# 3-channel_geo_amplifier.net
KiCad netlist of a schematic drawn in EAGLE
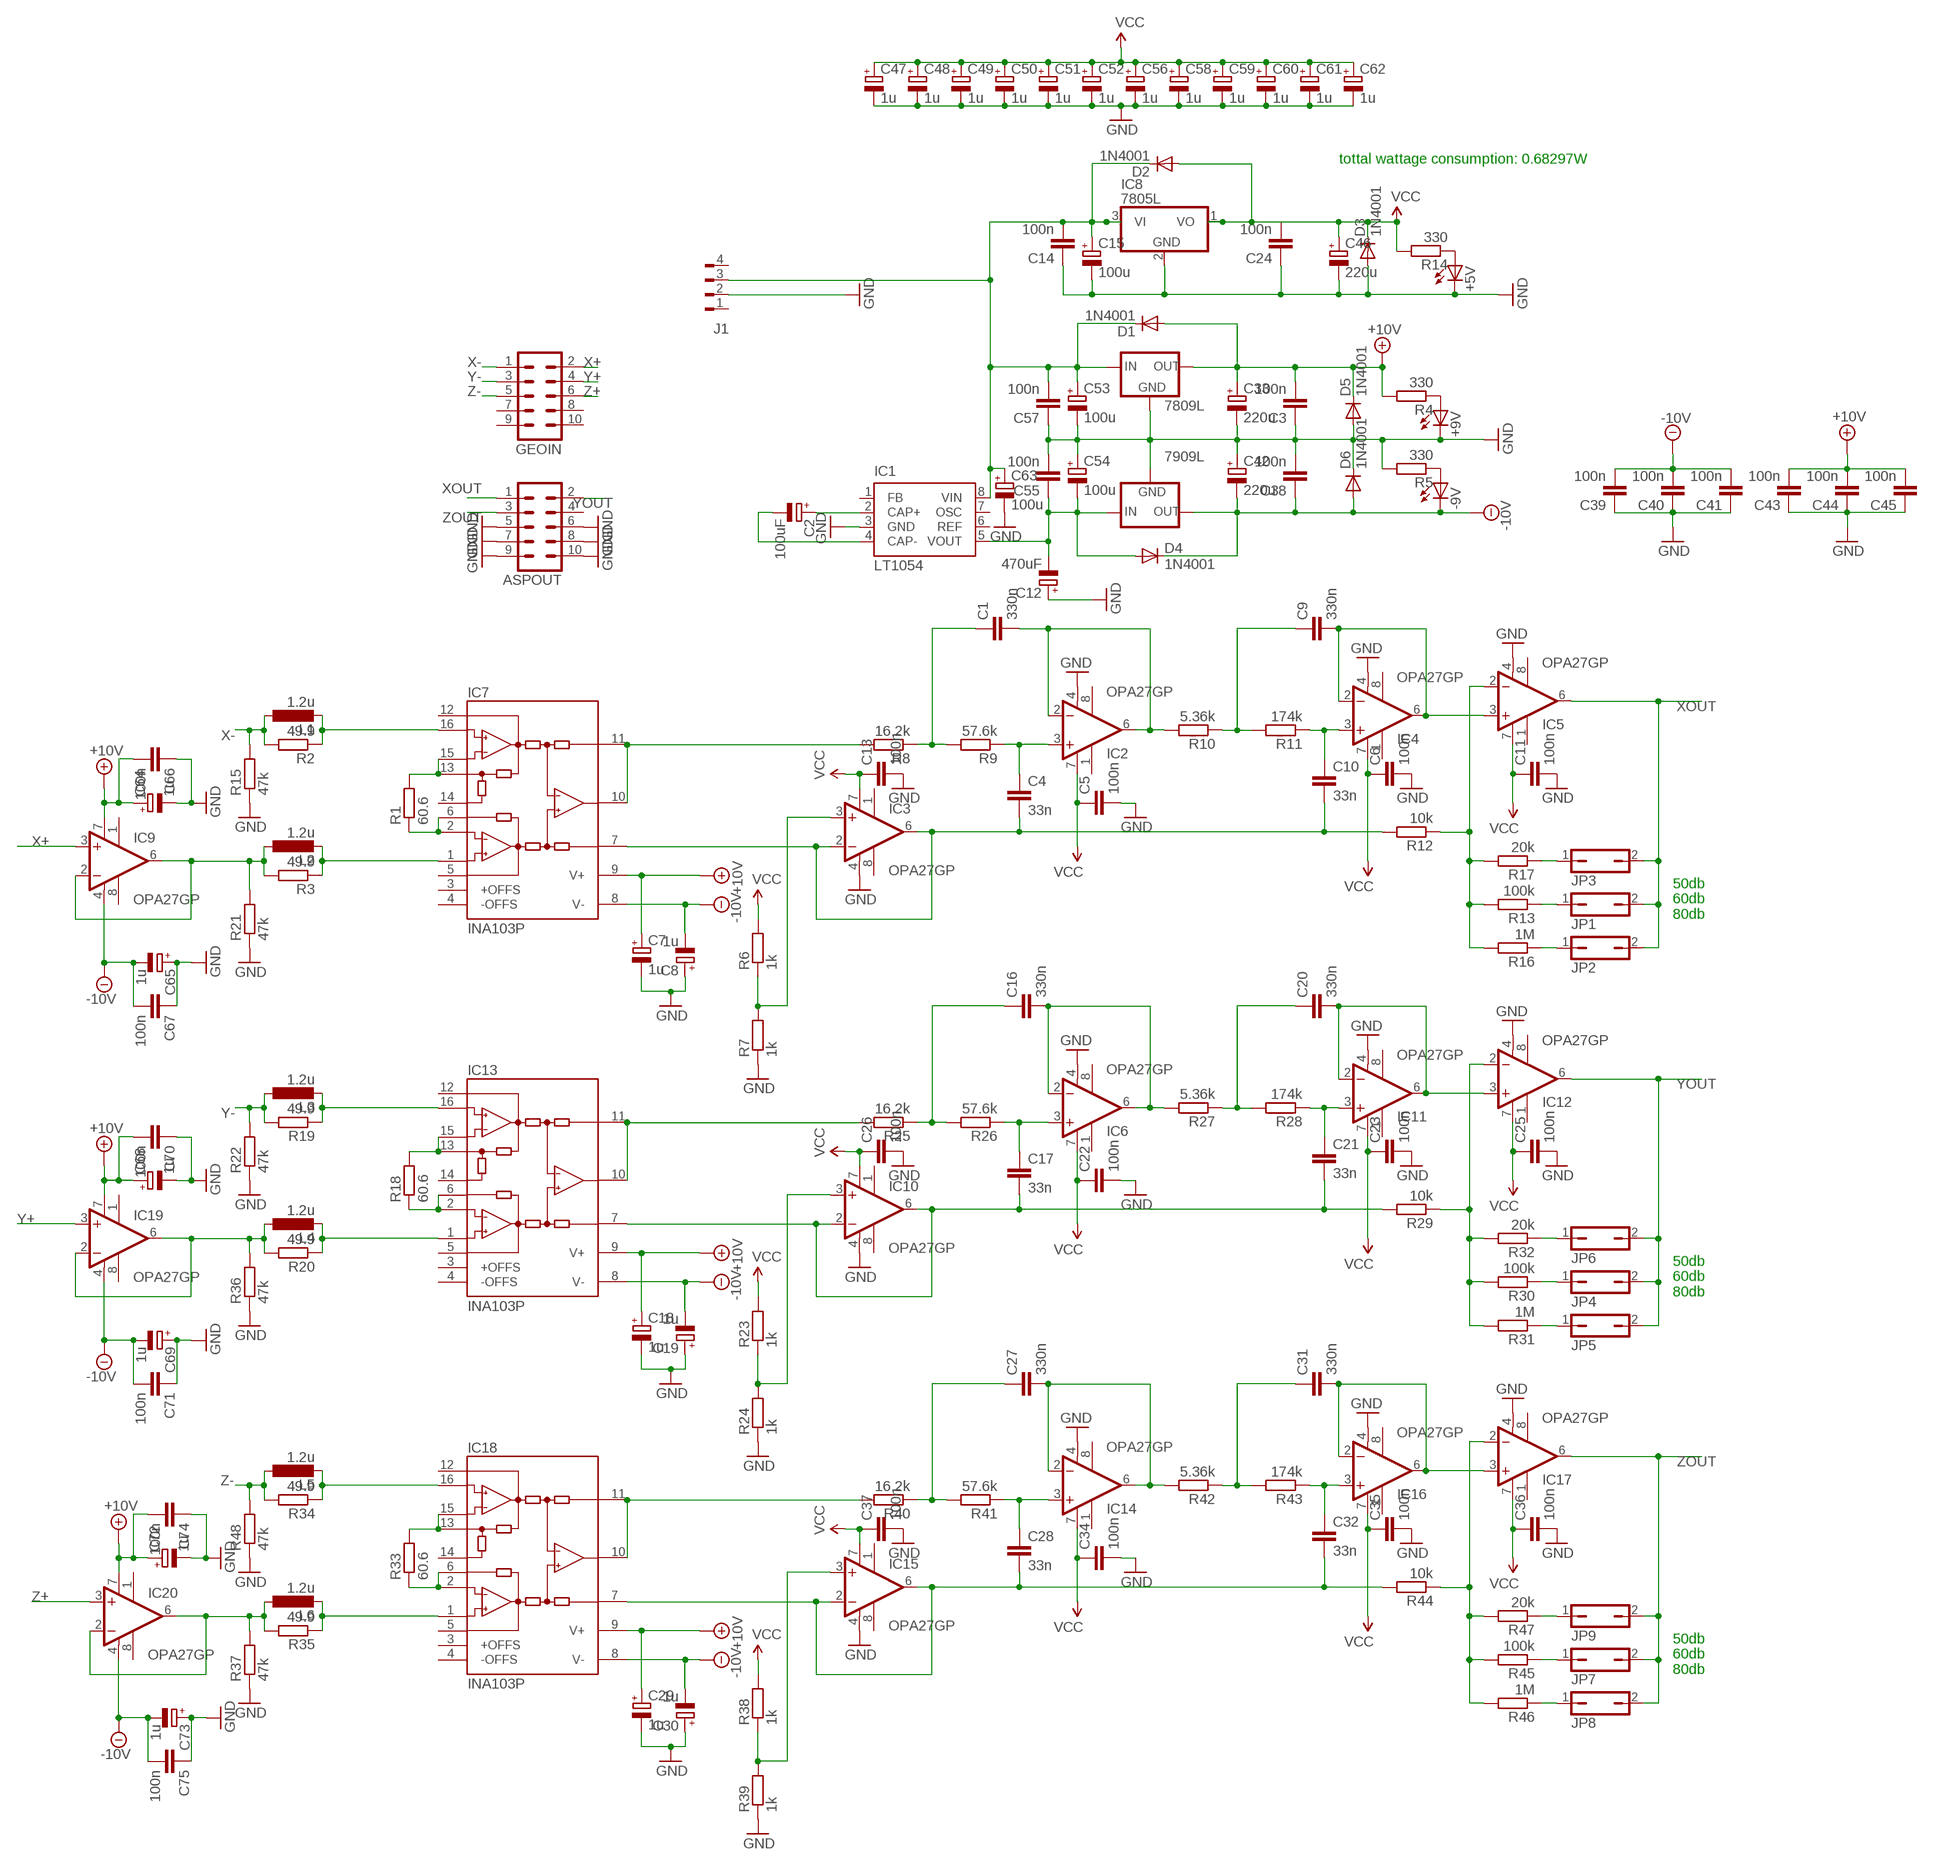
[diagram p0: schematic, sheet 1]

(export (version "E")
  (design (tool "Eeschema 10.0.6"))
  (components
    (comp (ref "+5V")
      (value "LED3MM")
      (footprint "eagle-import:LED3MM")
      (libsource (lib "eagle-import") (part "LED3MM"))
    )
    (comp (ref "+9V")
      (value "LED3MM")
      (footprint "eagle-import:LED3MM")
      (libsource (lib "eagle-import") (part "LED3MM"))
    )
    (comp (ref "-9V")
      (value "LED3MM")
      (footprint "eagle-import:LED3MM")
      (libsource (lib "eagle-import") (part "LED3MM"))
    )
    (comp (ref "7809L")
      (value "78LXX")
      (footprint "eagle-import:78LXX")
      (libsource (lib "eagle-import") (part "78LXX"))
    )
    (comp (ref "7909L")
      (value "79LXX")
      (footprint "eagle-import:79LXX")
      (libsource (lib "eagle-import") (part "79LXX"))
    )
    (comp (ref "ASPOUT")
      (value "ML10")
      (footprint "eagle-import:ML10")
      (libsource (lib "eagle-import") (part "ML10"))
    )
    (comp (ref "C1")
      (value "330n")
      (footprint "eagle-import:C050-025X075")
      (libsource (lib "eagle-import") (part "C-EU050-025X075"))
    )
    (comp (ref "C2")
      (value "100uF")
      (footprint "eagle-import:E2,5-7")
      (libsource (lib "eagle-import") (part "CPOL-EUE2.5-7"))
    )
    (comp (ref "C3")
      (value "100n")
      (footprint "eagle-import:C050-025X075")
      (libsource (lib "eagle-import") (part "C-EU050-025X075"))
    )
    (comp (ref "C4")
      (value "33n")
      (footprint "eagle-import:C050-025X075")
      (libsource (lib "eagle-import") (part "C-EU050-025X075"))
    )
    (comp (ref "C5")
      (value "100n")
      (footprint "eagle-import:C050-025X075")
      (libsource (lib "eagle-import") (part "C-EU050-025X075"))
    )
    (comp (ref "C6")
      (value "100n")
      (footprint "eagle-import:C050-025X075")
      (libsource (lib "eagle-import") (part "C-EU050-025X075"))
    )
    (comp (ref "C7")
      (value "1u")
      (footprint "eagle-import:B45181A")
      (libsource (lib "eagle-import") (part "CPOL-EUB45181A"))
    )
    (comp (ref "C8")
      (value "1u")
      (footprint "eagle-import:B45181A")
      (libsource (lib "eagle-import") (part "CPOL-EUB45181A"))
    )
    (comp (ref "C9")
      (value "330n")
      (footprint "eagle-import:C050-025X075")
      (libsource (lib "eagle-import") (part "C-EU050-025X075"))
    )
    (comp (ref "C10")
      (value "33n")
      (footprint "eagle-import:C050-025X075")
      (libsource (lib "eagle-import") (part "C-EU050-025X075"))
    )
    (comp (ref "C11")
      (value "100n")
      (footprint "eagle-import:C050-025X075")
      (libsource (lib "eagle-import") (part "C-EU050-025X075"))
    )
    (comp (ref "C12")
      (value "470uF")
      (footprint "eagle-import:E5-8,5")
      (libsource (lib "eagle-import") (part "CPOL-EUE5-8.5"))
    )
    (comp (ref "C13")
      (value "100n")
      (footprint "eagle-import:C050-025X075")
      (libsource (lib "eagle-import") (part "C-EU050-025X075"))
    )
    (comp (ref "C14")
      (value "100n")
      (footprint "eagle-import:C050-025X075")
      (libsource (lib "eagle-import") (part "C-EU050-025X075"))
    )
    (comp (ref "C15")
      (value "100u")
      (footprint "eagle-import:E2,5-7")
      (libsource (lib "eagle-import") (part "CPOL-EUE2.5-7"))
    )
    (comp (ref "C16")
      (value "330n")
      (footprint "eagle-import:C050-025X075")
      (libsource (lib "eagle-import") (part "C-EU050-025X075"))
    )
    (comp (ref "C17")
      (value "33n")
      (footprint "eagle-import:C050-025X075")
      (libsource (lib "eagle-import") (part "C-EU050-025X075"))
    )
    (comp (ref "C18")
      (value "1u")
      (footprint "eagle-import:B45181A")
      (libsource (lib "eagle-import") (part "CPOL-EUB45181A"))
    )
    (comp (ref "C19")
      (value "1u")
      (footprint "eagle-import:B45181A")
      (libsource (lib "eagle-import") (part "CPOL-EUB45181A"))
    )
    (comp (ref "C20")
      (value "330n")
      (footprint "eagle-import:C050-025X075")
      (libsource (lib "eagle-import") (part "C-EU050-025X075"))
    )
    (comp (ref "C21")
      (value "33n")
      (footprint "eagle-import:C050-025X075")
      (libsource (lib "eagle-import") (part "C-EU050-025X075"))
    )
    (comp (ref "C22")
      (value "100n")
      (footprint "eagle-import:C050-025X075")
      (libsource (lib "eagle-import") (part "C-EU050-025X075"))
    )
    (comp (ref "C23")
      (value "100n")
      (footprint "eagle-import:C050-025X075")
      (libsource (lib "eagle-import") (part "C-EU050-025X075"))
    )
    (comp (ref "C24")
      (value "100n")
      (footprint "eagle-import:C050-025X075")
      (libsource (lib "eagle-import") (part "C-EU050-025X075"))
    )
    (comp (ref "C25")
      (value "100n")
      (footprint "eagle-import:C050-025X075")
      (libsource (lib "eagle-import") (part "C-EU050-025X075"))
    )
    (comp (ref "C26")
      (value "100n")
      (footprint "eagle-import:C050-025X075")
      (libsource (lib "eagle-import") (part "C-EU050-025X075"))
    )
    (comp (ref "C27")
      (value "330n")
      (footprint "eagle-import:C050-025X075")
      (libsource (lib "eagle-import") (part "C-EU050-025X075"))
    )
    (comp (ref "C28")
      (value "33n")
      (footprint "eagle-import:C050-025X075")
      (libsource (lib "eagle-import") (part "C-EU050-025X075"))
    )
    (comp (ref "C29")
      (value "1u")
      (footprint "eagle-import:B45181A")
      (libsource (lib "eagle-import") (part "CPOL-EUB45181A"))
    )
    (comp (ref "C30")
      (value "1u")
      (footprint "eagle-import:B45181A")
      (libsource (lib "eagle-import") (part "CPOL-EUB45181A"))
    )
    (comp (ref "C31")
      (value "330n")
      (footprint "eagle-import:C050-025X075")
      (libsource (lib "eagle-import") (part "C-EU050-025X075"))
    )
    (comp (ref "C32")
      (value "33n")
      (footprint "eagle-import:C050-025X075")
      (libsource (lib "eagle-import") (part "C-EU050-025X075"))
    )
    (comp (ref "C33")
      (value "220u")
      (footprint "eagle-import:E2,5-5")
      (libsource (lib "eagle-import") (part "CPOL-EUE2.5-5"))
    )
    (comp (ref "C34")
      (value "100n")
      (footprint "eagle-import:C050-025X075")
      (libsource (lib "eagle-import") (part "C-EU050-025X075"))
    )
    (comp (ref "C35")
      (value "100n")
      (footprint "eagle-import:C050-025X075")
      (libsource (lib "eagle-import") (part "C-EU050-025X075"))
    )
    (comp (ref "C36")
      (value "100n")
      (footprint "eagle-import:C050-025X075")
      (libsource (lib "eagle-import") (part "C-EU050-025X075"))
    )
    (comp (ref "C37")
      (value "100n")
      (footprint "eagle-import:C050-025X075")
      (libsource (lib "eagle-import") (part "C-EU050-025X075"))
    )
    (comp (ref "C38")
      (value "100n")
      (footprint "eagle-import:C050-025X075")
      (libsource (lib "eagle-import") (part "C-EU050-025X075"))
    )
    (comp (ref "C39")
      (value "100n")
      (footprint "eagle-import:C050-025X075")
      (libsource (lib "eagle-import") (part "C-EU050-025X075"))
    )
    (comp (ref "C40")
      (value "100n")
      (footprint "eagle-import:C050-025X075")
      (libsource (lib "eagle-import") (part "C-EU050-025X075"))
    )
    (comp (ref "C41")
      (value "100n")
      (footprint "eagle-import:C050-025X075")
      (libsource (lib "eagle-import") (part "C-EU050-025X075"))
    )
    (comp (ref "C42")
      (value "220u")
      (footprint "eagle-import:E2,5-5")
      (libsource (lib "eagle-import") (part "CPOL-EUE2.5-5"))
    )
    (comp (ref "C43")
      (value "100n")
      (footprint "eagle-import:C050-025X075")
      (libsource (lib "eagle-import") (part "C-EU050-025X075"))
    )
    (comp (ref "C44")
      (value "100n")
      (footprint "eagle-import:C050-025X075")
      (libsource (lib "eagle-import") (part "C-EU050-025X075"))
    )
    (comp (ref "C45")
      (value "100n")
      (footprint "eagle-import:C050-025X075")
      (libsource (lib "eagle-import") (part "C-EU050-025X075"))
    )
    (comp (ref "C46")
      (value "220u")
      (footprint "eagle-import:E2,5-7")
      (libsource (lib "eagle-import") (part "CPOL-EUE2.5-7"))
    )
    (comp (ref "C47")
      (value "1u")
      (footprint "eagle-import:B45181A")
      (libsource (lib "eagle-import") (part "CPOL-EUB45181A"))
    )
    (comp (ref "C48")
      (value "1u")
      (footprint "eagle-import:B45181A")
      (libsource (lib "eagle-import") (part "CPOL-EUB45181A"))
    )
    (comp (ref "C49")
      (value "1u")
      (footprint "eagle-import:B45181A")
      (libsource (lib "eagle-import") (part "CPOL-EUB45181A"))
    )
    (comp (ref "C50")
      (value "1u")
      (footprint "eagle-import:B45181A")
      (libsource (lib "eagle-import") (part "CPOL-EUB45181A"))
    )
    (comp (ref "C51")
      (value "1u")
      (footprint "eagle-import:B45181A")
      (libsource (lib "eagle-import") (part "CPOL-EUB45181A"))
    )
    (comp (ref "C52")
      (value "1u")
      (footprint "eagle-import:B45181A")
      (libsource (lib "eagle-import") (part "CPOL-EUB45181A"))
    )
    (comp (ref "C53")
      (value "100u")
      (footprint "eagle-import:E2,5-5")
      (libsource (lib "eagle-import") (part "CPOL-EUE2.5-5"))
    )
    (comp (ref "C54")
      (value "100u")
      (footprint "eagle-import:E2,5-5")
      (libsource (lib "eagle-import") (part "CPOL-EUE2.5-5"))
    )
    (comp (ref "C55")
      (value "100n")
      (footprint "eagle-import:C050-025X075")
      (libsource (lib "eagle-import") (part "C-EU050-025X075"))
    )
    (comp (ref "C56")
      (value "1u")
      (footprint "eagle-import:B45181A")
      (libsource (lib "eagle-import") (part "CPOL-EUB45181A"))
    )
    (comp (ref "C57")
      (value "100n")
      (footprint "eagle-import:C050-025X075")
      (libsource (lib "eagle-import") (part "C-EU050-025X075"))
    )
    (comp (ref "C58")
      (value "1u")
      (footprint "eagle-import:B45181A")
      (libsource (lib "eagle-import") (part "CPOL-EUB45181A"))
    )
    (comp (ref "C59")
      (value "1u")
      (footprint "eagle-import:B45181A")
      (libsource (lib "eagle-import") (part "CPOL-EUB45181A"))
    )
    (comp (ref "C60")
      (value "1u")
      (footprint "eagle-import:B45181A")
      (libsource (lib "eagle-import") (part "CPOL-EUB45181A"))
    )
    (comp (ref "C61")
      (value "1u")
      (footprint "eagle-import:B45181A")
      (libsource (lib "eagle-import") (part "CPOL-EUB45181A"))
    )
    (comp (ref "C62")
      (value "1u")
      (footprint "eagle-import:B45181A")
      (libsource (lib "eagle-import") (part "CPOL-EUB45181A"))
    )
    (comp (ref "C63")
      (value "100u")
      (footprint "eagle-import:E2,5-5")
      (libsource (lib "eagle-import") (part "CPOL-EUE2.5-5"))
    )
    (comp (ref "C64")
      (value "1u")
      (footprint "eagle-import:B45181A")
      (libsource (lib "eagle-import") (part "CPOL-EUB45181A"))
    )
    (comp (ref "C65")
      (value "1u")
      (footprint "eagle-import:B45181A")
      (libsource (lib "eagle-import") (part "CPOL-EUB45181A"))
    )
    (comp (ref "C66")
      (value "100n")
      (footprint "eagle-import:C050-025X075")
      (libsource (lib "eagle-import") (part "C-EU050-025X075"))
    )
    (comp (ref "C67")
      (value "100n")
      (footprint "eagle-import:C050-025X075")
      (libsource (lib "eagle-import") (part "C-EU050-025X075"))
    )
    (comp (ref "C68")
      (value "1u")
      (footprint "eagle-import:B45181A")
      (libsource (lib "eagle-import") (part "CPOL-EUB45181A"))
    )
    (comp (ref "C69")
      (value "1u")
      (footprint "eagle-import:B45181A")
      (libsource (lib "eagle-import") (part "CPOL-EUB45181A"))
    )
    (comp (ref "C70")
      (value "100n")
      (footprint "eagle-import:C050-025X075")
      (libsource (lib "eagle-import") (part "C-EU050-025X075"))
    )
    (comp (ref "C71")
      (value "100n")
      (footprint "eagle-import:C050-025X075")
      (libsource (lib "eagle-import") (part "C-EU050-025X075"))
    )
    (comp (ref "C72")
      (value "1u")
      (footprint "eagle-import:B45181A")
      (libsource (lib "eagle-import") (part "CPOL-EUB45181A"))
    )
    (comp (ref "C73")
      (value "1u")
      (footprint "eagle-import:B45181A")
      (libsource (lib "eagle-import") (part "CPOL-EUB45181A"))
    )
    (comp (ref "C74")
      (value "100n")
      (footprint "eagle-import:C050-025X075")
      (libsource (lib "eagle-import") (part "C-EU050-025X075"))
    )
    (comp (ref "C75")
      (value "100n")
      (footprint "eagle-import:C050-025X075")
      (libsource (lib "eagle-import") (part "C-EU050-025X075"))
    )
    (comp (ref "D1")
      (value "1N4001")
      (footprint "eagle-import:DO41-10")
      (libsource (lib "eagle-import") (part "1N4004"))
    )
    (comp (ref "D2")
      (value "1N4001")
      (footprint "eagle-import:DO41-10")
      (libsource (lib "eagle-import") (part "1N4004"))
    )
    (comp (ref "D3")
      (value "1N4001")
      (footprint "eagle-import:DO41-10")
      (libsource (lib "eagle-import") (part "1N4004"))
    )
    (comp (ref "D4")
      (value "1N4001")
      (footprint "eagle-import:DO41-10")
      (libsource (lib "eagle-import") (part "1N4004"))
    )
    (comp (ref "D5")
      (value "1N4001")
      (footprint "eagle-import:DO41-10")
      (libsource (lib "eagle-import") (part "1N4004"))
    )
    (comp (ref "D6")
      (value "1N4001")
      (footprint "eagle-import:DO41-10")
      (libsource (lib "eagle-import") (part "1N4004"))
    )
    (comp (ref "GEOIN")
      (value "ML10")
      (footprint "eagle-import:ML10")
      (libsource (lib "eagle-import") (part "ML10"))
    )
    (comp (ref "IC1")
      (value "LT1054")
      (footprint "eagle-import:DIL8")
      (libsource (lib "eagle-import") (part "LT1054"))
    )
    (comp (ref "IC2")
      (value "OPA27GP")
      (footprint "eagle-import:DIL08")
      (libsource (lib "eagle-import") (part "OPA?GP27"))
    )
    (comp (ref "IC3")
      (value "OPA27GP")
      (footprint "eagle-import:DIL08")
      (libsource (lib "eagle-import") (part "OPA?GP27"))
    )
    (comp (ref "IC4")
      (value "OPA27GP")
      (footprint "eagle-import:DIL08")
      (libsource (lib "eagle-import") (part "OPA?GP27"))
    )
    (comp (ref "IC5")
      (value "OPA27GP")
      (footprint "eagle-import:DIL08")
      (libsource (lib "eagle-import") (part "OPA?GP27"))
    )
    (comp (ref "IC6")
      (value "OPA27GP")
      (footprint "eagle-import:DIL08")
      (libsource (lib "eagle-import") (part "OPA?GP27"))
    )
    (comp (ref "IC7")
      (value "INA103P")
      (footprint "eagle-import:DIL16")
      (fields (field (name "MF") "TEXAS INSTRUMENTS") (field (name "MPN") "INA103KP"))
      (libsource (lib "eagle-import") (part "INA103P"))
    )
    (comp (ref "IC8")
      (value "7805L")
      (footprint "eagle-import:TO92")
      (libsource (lib "eagle-import") (part "78L05"))
    )
    (comp (ref "IC9")
      (value "OPA27GP")
      (footprint "eagle-import:DIL08")
      (libsource (lib "eagle-import") (part "OPA?GP27"))
    )
    (comp (ref "IC10")
      (value "OPA27GP")
      (footprint "eagle-import:DIL08")
      (libsource (lib "eagle-import") (part "OPA?GP27"))
    )
    (comp (ref "IC11")
      (value "OPA27GP")
      (footprint "eagle-import:DIL08")
      (libsource (lib "eagle-import") (part "OPA?GP27"))
    )
    (comp (ref "IC12")
      (value "OPA27GP")
      (footprint "eagle-import:DIL08")
      (libsource (lib "eagle-import") (part "OPA?GP27"))
    )
    (comp (ref "IC13")
      (value "INA103P")
      (footprint "eagle-import:DIL16")
      (fields (field (name "MF") "TEXAS INSTRUMENTS") (field (name "MPN") "INA103KP"))
      (libsource (lib "eagle-import") (part "INA103P"))
    )
    (comp (ref "IC14")
      (value "OPA27GP")
      (footprint "eagle-import:DIL08")
      (libsource (lib "eagle-import") (part "OPA?GP27"))
    )
    (comp (ref "IC15")
      (value "OPA27GP")
      (footprint "eagle-import:DIL08")
      (libsource (lib "eagle-import") (part "OPA?GP27"))
    )
    (comp (ref "IC16")
      (value "OPA27GP")
      (footprint "eagle-import:DIL08")
      (libsource (lib "eagle-import") (part "OPA?GP27"))
    )
    (comp (ref "IC17")
      (value "OPA27GP")
      (footprint "eagle-import:DIL08")
      (libsource (lib "eagle-import") (part "OPA?GP27"))
    )
    (comp (ref "IC18")
      (value "INA103P")
      (footprint "eagle-import:DIL16")
      (fields (field (name "MF") "TEXAS INSTRUMENTS") (field (name "MPN") "INA103KP"))
      (libsource (lib "eagle-import") (part "INA103P"))
    )
    (comp (ref "IC19")
      (value "OPA27GP")
      (footprint "eagle-import:DIL08")
      (libsource (lib "eagle-import") (part "OPA?GP27"))
    )
    (comp (ref "IC20")
      (value "OPA27GP")
      (footprint "eagle-import:DIL08")
      (libsource (lib "eagle-import") (part "OPA?GP27"))
    )
    (comp (ref "J1")
      (value "FLOP-4W827001")
      (footprint "eagle-import:827001")
      (libsource (lib "eagle-import") (part "FLOP-4W827001"))
    )
    (comp (ref "JP1")
      (value "JP1Q")
      (footprint "eagle-import:JP1")
      (libsource (lib "eagle-import") (part "JP1Q"))
    )
    (comp (ref "JP2")
      (value "JP1Q")
      (footprint "eagle-import:JP1")
      (libsource (lib "eagle-import") (part "JP1Q"))
    )
    (comp (ref "JP3")
      (value "JP1Q")
      (footprint "eagle-import:JP1")
      (libsource (lib "eagle-import") (part "JP1Q"))
    )
    (comp (ref "JP4")
      (value "JP1Q")
      (footprint "eagle-import:JP1")
      (libsource (lib "eagle-import") (part "JP1Q"))
    )
    (comp (ref "JP5")
      (value "JP1Q")
      (footprint "eagle-import:JP1")
      (libsource (lib "eagle-import") (part "JP1Q"))
    )
    (comp (ref "JP6")
      (value "JP1Q")
      (footprint "eagle-import:JP1")
      (libsource (lib "eagle-import") (part "JP1Q"))
    )
    (comp (ref "JP7")
      (value "JP1Q")
      (footprint "eagle-import:JP1")
      (libsource (lib "eagle-import") (part "JP1Q"))
    )
    (comp (ref "JP8")
      (value "JP1Q")
      (footprint "eagle-import:JP1")
      (libsource (lib "eagle-import") (part "JP1Q"))
    )
    (comp (ref "JP9")
      (value "JP1Q")
      (footprint "eagle-import:JP1")
      (libsource (lib "eagle-import") (part "JP1Q"))
    )
    (comp (ref "L1")
      (value "1.2u")
      (footprint "eagle-import:0207_10")
      (libsource (lib "eagle-import") (part "L-EU0207/10"))
    )
    (comp (ref "L2")
      (value "1.2u")
      (footprint "eagle-import:0207_10")
      (libsource (lib "eagle-import") (part "L-EU0207/10"))
    )
    (comp (ref "L3")
      (value "1.2u")
      (footprint "eagle-import:0207_10")
      (libsource (lib "eagle-import") (part "L-EU0207/10"))
    )
    (comp (ref "L4")
      (value "1.2u")
      (footprint "eagle-import:0207_10")
      (libsource (lib "eagle-import") (part "L-EU0207/10"))
    )
    (comp (ref "L5")
      (value "1.2u")
      (footprint "eagle-import:0207_10")
      (libsource (lib "eagle-import") (part "L-EU0207/10"))
    )
    (comp (ref "L6")
      (value "1.2u")
      (footprint "eagle-import:0207_10")
      (libsource (lib "eagle-import") (part "L-EU0207/10"))
    )
    (comp (ref "R1")
      (value "60.6")
      (footprint "eagle-import:0207_10")
      (libsource (lib "eagle-import") (part "R-EU_0207/10"))
    )
    (comp (ref "R2")
      (value "49.9")
      (footprint "eagle-import:0207_10")
      (libsource (lib "eagle-import") (part "R-EU_0207/10"))
    )
    (comp (ref "R3")
      (value "49.9")
      (footprint "eagle-import:0207_10")
      (libsource (lib "eagle-import") (part "R-EU_0207/10"))
    )
    (comp (ref "R4")
      (value "330")
      (footprint "eagle-import:0207_10")
      (libsource (lib "eagle-import") (part "R-EU_0207/10"))
    )
    (comp (ref "R5")
      (value "330")
      (footprint "eagle-import:0207_10")
      (libsource (lib "eagle-import") (part "R-EU_0207/10"))
    )
    (comp (ref "R6")
      (value "1k")
      (footprint "eagle-import:0207_10")
      (libsource (lib "eagle-import") (part "R-EU_0207/10"))
    )
    (comp (ref "R7")
      (value "1k")
      (footprint "eagle-import:0207_10")
      (libsource (lib "eagle-import") (part "R-EU_0207/10"))
    )
    (comp (ref "R8")
      (value "16.2k")
      (footprint "eagle-import:0207_10")
      (libsource (lib "eagle-import") (part "R-EU_0207/10"))
    )
    (comp (ref "R9")
      (value "57.6k")
      (footprint "eagle-import:0207_10")
      (libsource (lib "eagle-import") (part "R-EU_0207/10"))
    )
    (comp (ref "R10")
      (value "5.36k")
      (footprint "eagle-import:0207_10")
      (libsource (lib "eagle-import") (part "R-EU_0207/10"))
    )
    (comp (ref "R11")
      (value "174k")
      (footprint "eagle-import:0207_10")
      (libsource (lib "eagle-import") (part "R-EU_0207/10"))
    )
    (comp (ref "R12")
      (value "10k")
      (footprint "eagle-import:0207_10")
      (libsource (lib "eagle-import") (part "R-EU_0207/10"))
    )
    (comp (ref "R13")
      (value "100k")
      (footprint "eagle-import:0207_10")
      (libsource (lib "eagle-import") (part "R-EU_0207/10"))
    )
    (comp (ref "R14")
      (value "330")
      (footprint "eagle-import:0207_10")
      (libsource (lib "eagle-import") (part "R-EU_0207/10"))
    )
    (comp (ref "R15")
      (value "47k")
      (footprint "eagle-import:0207_10")
      (libsource (lib "eagle-import") (part "R-EU_0207/10"))
    )
    (comp (ref "R16")
      (value "1M")
      (footprint "eagle-import:0207_10")
      (libsource (lib "eagle-import") (part "R-EU_0207/10"))
    )
    (comp (ref "R17")
      (value "20k")
      (footprint "eagle-import:0207_10")
      (libsource (lib "eagle-import") (part "R-EU_0207/10"))
    )
    (comp (ref "R18")
      (value "60.6")
      (footprint "eagle-import:0207_10")
      (libsource (lib "eagle-import") (part "R-EU_0207/10"))
    )
    (comp (ref "R19")
      (value "49.9")
      (footprint "eagle-import:0207_10")
      (libsource (lib "eagle-import") (part "R-EU_0207/10"))
    )
    (comp (ref "R20")
      (value "49.9")
      (footprint "eagle-import:0207_10")
      (libsource (lib "eagle-import") (part "R-EU_0207/10"))
    )
    (comp (ref "R21")
      (value "47k")
      (footprint "eagle-import:0207_10")
      (libsource (lib "eagle-import") (part "R-EU_0207/10"))
    )
    (comp (ref "R22")
      (value "47k")
      (footprint "eagle-import:0207_10")
      (libsource (lib "eagle-import") (part "R-EU_0207/10"))
    )
    (comp (ref "R23")
      (value "1k")
      (footprint "eagle-import:0207_10")
      (libsource (lib "eagle-import") (part "R-EU_0207/10"))
    )
    (comp (ref "R24")
      (value "1k")
      (footprint "eagle-import:0207_10")
      (libsource (lib "eagle-import") (part "R-EU_0207/10"))
    )
    (comp (ref "R25")
      (value "16.2k")
      (footprint "eagle-import:0207_10")
      (libsource (lib "eagle-import") (part "R-EU_0207/10"))
    )
    (comp (ref "R26")
      (value "57.6k")
      (footprint "eagle-import:0207_10")
      (libsource (lib "eagle-import") (part "R-EU_0207/10"))
    )
    (comp (ref "R27")
      (value "5.36k")
      (footprint "eagle-import:0207_10")
      (libsource (lib "eagle-import") (part "R-EU_0207/10"))
    )
    (comp (ref "R28")
      (value "174k")
      (footprint "eagle-import:0207_10")
      (libsource (lib "eagle-import") (part "R-EU_0207/10"))
    )
    (comp (ref "R29")
      (value "10k")
      (footprint "eagle-import:0207_10")
      (libsource (lib "eagle-import") (part "R-EU_0207/10"))
    )
    (comp (ref "R30")
      (value "100k")
      (footprint "eagle-import:0207_10")
      (libsource (lib "eagle-import") (part "R-EU_0207/10"))
    )
    (comp (ref "R31")
      (value "1M")
      (footprint "eagle-import:0207_10")
      (libsource (lib "eagle-import") (part "R-EU_0207/10"))
    )
    (comp (ref "R32")
      (value "20k")
      (footprint "eagle-import:0207_10")
      (libsource (lib "eagle-import") (part "R-EU_0207/10"))
    )
    (comp (ref "R33")
      (value "60.6")
      (footprint "eagle-import:0207_10")
      (libsource (lib "eagle-import") (part "R-EU_0207/10"))
    )
    (comp (ref "R34")
      (value "49.9")
      (footprint "eagle-import:0207_10")
      (libsource (lib "eagle-import") (part "R-EU_0207/10"))
    )
    (comp (ref "R35")
      (value "49.9")
      (footprint "eagle-import:0207_10")
      (libsource (lib "eagle-import") (part "R-EU_0207/10"))
    )
    (comp (ref "R36")
      (value "47k")
      (footprint "eagle-import:0207_10")
      (libsource (lib "eagle-import") (part "R-EU_0207/10"))
    )
    (comp (ref "R37")
      (value "47k")
      (footprint "eagle-import:0207_10")
      (libsource (lib "eagle-import") (part "R-EU_0207/10"))
    )
    (comp (ref "R38")
      (value "1k")
      (footprint "eagle-import:0207_10")
      (libsource (lib "eagle-import") (part "R-EU_0207/10"))
    )
    (comp (ref "R39")
      (value "1k")
      (footprint "eagle-import:0207_10")
      (libsource (lib "eagle-import") (part "R-EU_0207/10"))
    )
    (comp (ref "R40")
      (value "16.2k")
      (footprint "eagle-import:0207_10")
      (libsource (lib "eagle-import") (part "R-EU_0207/10"))
    )
    (comp (ref "R41")
      (value "57.6k")
      (footprint "eagle-import:0207_10")
      (libsource (lib "eagle-import") (part "R-EU_0207/10"))
    )
    (comp (ref "R42")
      (value "5.36k")
      (footprint "eagle-import:0207_10")
      (libsource (lib "eagle-import") (part "R-EU_0207/10"))
    )
    (comp (ref "R43")
      (value "174k")
      (footprint "eagle-import:0207_10")
      (libsource (lib "eagle-import") (part "R-EU_0207/10"))
    )
    (comp (ref "R44")
      (value "10k")
      (footprint "eagle-import:0207_10")
      (libsource (lib "eagle-import") (part "R-EU_0207/10"))
    )
    (comp (ref "R45")
      (value "100k")
      (footprint "eagle-import:0207_10")
      (libsource (lib "eagle-import") (part "R-EU_0207/10"))
    )
    (comp (ref "R46")
      (value "1M")
      (footprint "eagle-import:0207_10")
      (libsource (lib "eagle-import") (part "R-EU_0207/10"))
    )
    (comp (ref "R47")
      (value "20k")
      (footprint "eagle-import:0207_10")
      (libsource (lib "eagle-import") (part "R-EU_0207/10"))
    )
    (comp (ref "R48")
      (value "47k")
      (footprint "eagle-import:0207_10")
      (libsource (lib "eagle-import") (part "R-EU_0207/10"))
    )
  )
  (nets
    (net (code "1") (name "+10V") (class "Default")
      (node (ref "7809L") (pin "OUT") (pinfunction "OUT_OUT") (pintype "passive"))
      (node (ref "C18") (pin "+") (pinfunction "+_+") (pintype "passive"))
      (node (ref "C29") (pin "+") (pinfunction "+_+") (pintype "passive"))
      (node (ref "C3") (pin "2") (pinfunction "2_2") (pintype "passive"))
      (node (ref "C33") (pin "+") (pinfunction "+_+") (pintype "passive"))
      (node (ref "C43") (pin "2") (pinfunction "2_2") (pintype "passive"))
      (node (ref "C44") (pin "2") (pinfunction "2_2") (pintype "passive"))
      (node (ref "C45") (pin "2") (pinfunction "2_2") (pintype "passive"))
      (node (ref "C64") (pin "+") (pinfunction "+_+") (pintype "passive"))
      (node (ref "C66") (pin "2") (pinfunction "2_2") (pintype "passive"))
      (node (ref "C68") (pin "+") (pinfunction "+_+") (pintype "passive"))
      (node (ref "C7") (pin "+") (pinfunction "+_+") (pintype "passive"))
      (node (ref "C70") (pin "2") (pinfunction "2_2") (pintype "passive"))
      (node (ref "C72") (pin "+") (pinfunction "+_+") (pintype "passive"))
      (node (ref "C74") (pin "2") (pinfunction "2_2") (pintype "passive"))
      (node (ref "D1") (pin "A") (pinfunction "A_A") (pintype "passive"))
      (node (ref "D5") (pin "C") (pinfunction "C_C") (pintype "passive"))
      (node (ref "IC13") (pin "9") (pinfunction "V+_9") (pintype "power_in"))
      (node (ref "IC18") (pin "9") (pinfunction "V+_9") (pintype "power_in"))
      (node (ref "IC19") (pin "7") (pinfunction "V+_7") (pintype "power_in"))
      (node (ref "IC20") (pin "7") (pinfunction "V+_7") (pintype "power_in"))
      (node (ref "IC7") (pin "9") (pinfunction "V+_9") (pintype "power_in"))
      (node (ref "IC9") (pin "7") (pinfunction "V+_7") (pintype "power_in"))
      (node (ref "R4") (pin "2") (pinfunction "2_2") (pintype "passive"))
    )
    (net (code "2") (name "-10V") (class "Default")
      (node (ref "-9V") (pin "K") (pinfunction "C_K") (pintype "passive"))
      (node (ref "7909L") (pin "OUT") (pinfunction "OUT_OUT") (pintype "passive"))
      (node (ref "C19") (pin "-") (pinfunction "-_-") (pintype "passive"))
      (node (ref "C30") (pin "-") (pinfunction "-_-") (pintype "passive"))
      (node (ref "C38") (pin "1") (pinfunction "1_1") (pintype "passive"))
      (node (ref "C39") (pin "2") (pinfunction "2_2") (pintype "passive"))
      (node (ref "C40") (pin "2") (pinfunction "2_2") (pintype "passive"))
      (node (ref "C41") (pin "2") (pinfunction "2_2") (pintype "passive"))
      (node (ref "C42") (pin "-") (pinfunction "-_-") (pintype "passive"))
      (node (ref "C65") (pin "-") (pinfunction "-_-") (pintype "passive"))
      (node (ref "C67") (pin "2") (pinfunction "2_2") (pintype "passive"))
      (node (ref "C69") (pin "-") (pinfunction "-_-") (pintype "passive"))
      (node (ref "C71") (pin "2") (pinfunction "2_2") (pintype "passive"))
      (node (ref "C73") (pin "-") (pinfunction "-_-") (pintype "passive"))
      (node (ref "C75") (pin "2") (pinfunction "2_2") (pintype "passive"))
      (node (ref "C8") (pin "-") (pinfunction "-_-") (pintype "passive"))
      (node (ref "D4") (pin "C") (pinfunction "C_C") (pintype "passive"))
      (node (ref "D6") (pin "A") (pinfunction "A_A") (pintype "passive"))
      (node (ref "IC13") (pin "8") (pinfunction "V-_8") (pintype "power_in"))
      (node (ref "IC18") (pin "8") (pinfunction "V-_8") (pintype "power_in"))
      (node (ref "IC19") (pin "4") (pinfunction "V-_4") (pintype "power_in"))
      (node (ref "IC20") (pin "4") (pinfunction "V-_4") (pintype "power_in"))
      (node (ref "IC7") (pin "8") (pinfunction "V-_8") (pintype "power_in"))
      (node (ref "IC9") (pin "4") (pinfunction "V-_4") (pintype "power_in"))
    )
    (net (code "3") (name "/X+") (class "Default")
      (node (ref "GEOIN") (pin "2") (pinfunction "2_2") (pintype "passive"))
      (node (ref "IC9") (pin "3") (pinfunction "+IN_3") (pintype "input"))
    )
    (net (code "4") (name "/X-") (class "Default")
      (node (ref "GEOIN") (pin "1") (pinfunction "1_1") (pintype "passive"))
      (node (ref "L1") (pin "1") (pinfunction "1_1") (pintype "passive"))
      (node (ref "R15") (pin "2") (pinfunction "2_2") (pintype "passive"))
      (node (ref "R2") (pin "2") (pinfunction "2_2") (pintype "passive"))
    )
    (net (code "5") (name "/XOUT") (class "Default")
      (node (ref "ASPOUT") (pin "1") (pinfunction "1_1") (pintype "passive"))
      (node (ref "IC5") (pin "6") (pinfunction "OUT_6") (pintype "output"))
      (node (ref "JP1") (pin "2") (pinfunction "2_2") (pintype "passive"))
      (node (ref "JP2") (pin "2") (pinfunction "2_2") (pintype "passive"))
      (node (ref "JP3") (pin "2") (pinfunction "2_2") (pintype "passive"))
    )
    (net (code "6") (name "/Y+") (class "Default")
      (node (ref "GEOIN") (pin "4") (pinfunction "4_4") (pintype "passive"))
      (node (ref "IC19") (pin "3") (pinfunction "+IN_3") (pintype "input"))
    )
    (net (code "7") (name "/Y-") (class "Default")
      (node (ref "GEOIN") (pin "3") (pinfunction "3_3") (pintype "passive"))
      (node (ref "L3") (pin "1") (pinfunction "1_1") (pintype "passive"))
      (node (ref "R19") (pin "2") (pinfunction "2_2") (pintype "passive"))
      (node (ref "R22") (pin "2") (pinfunction "2_2") (pintype "passive"))
    )
    (net (code "8") (name "/YOUT") (class "Default")
      (node (ref "ASPOUT") (pin "2") (pinfunction "2_2") (pintype "passive"))
      (node (ref "IC12") (pin "6") (pinfunction "OUT_6") (pintype "output"))
      (node (ref "JP4") (pin "2") (pinfunction "2_2") (pintype "passive"))
      (node (ref "JP5") (pin "2") (pinfunction "2_2") (pintype "passive"))
      (node (ref "JP6") (pin "2") (pinfunction "2_2") (pintype "passive"))
    )
    (net (code "9") (name "/Z+") (class "Default")
      (node (ref "GEOIN") (pin "6") (pinfunction "6_6") (pintype "passive"))
      (node (ref "IC20") (pin "3") (pinfunction "+IN_3") (pintype "input"))
    )
    (net (code "10") (name "/Z-") (class "Default")
      (node (ref "GEOIN") (pin "5") (pinfunction "5_5") (pintype "passive"))
      (node (ref "L5") (pin "1") (pinfunction "1_1") (pintype "passive"))
      (node (ref "R34") (pin "2") (pinfunction "2_2") (pintype "passive"))
      (node (ref "R48") (pin "2") (pinfunction "2_2") (pintype "passive"))
    )
    (net (code "11") (name "/ZOUT") (class "Default")
      (node (ref "ASPOUT") (pin "3") (pinfunction "3_3") (pintype "passive"))
      (node (ref "IC17") (pin "6") (pinfunction "OUT_6") (pintype "output"))
      (node (ref "JP7") (pin "2") (pinfunction "2_2") (pintype "passive"))
      (node (ref "JP8") (pin "2") (pinfunction "2_2") (pintype "passive"))
      (node (ref "JP9") (pin "2") (pinfunction "2_2") (pintype "passive"))
    )
    (net (code "12") (name "GND") (class "Default")
      (node (ref "+5V") (pin "K") (pinfunction "C_K") (pintype "passive"))
      (node (ref "+9V") (pin "K") (pinfunction "C_K") (pintype "passive"))
      (node (ref "7809L") (pin "GND") (pinfunction "GND_GND") (pintype "input"))
      (node (ref "7909L") (pin "GND") (pinfunction "GND_GND") (pintype "input"))
      (node (ref "ASPOUT") (pin "10") (pinfunction "10_10") (pintype "passive"))
      (node (ref "ASPOUT") (pin "5") (pinfunction "5_5") (pintype "passive"))
      (node (ref "ASPOUT") (pin "6") (pinfunction "6_6") (pintype "passive"))
      (node (ref "ASPOUT") (pin "7") (pinfunction "7_7") (pintype "passive"))
      (node (ref "ASPOUT") (pin "8") (pinfunction "8_8") (pintype "passive"))
      (node (ref "ASPOUT") (pin "9") (pinfunction "9_9") (pintype "passive"))
      (node (ref "C11") (pin "2") (pinfunction "2_2") (pintype "passive"))
      (node (ref "C12") (pin "+") (pinfunction "+_+") (pintype "passive"))
      (node (ref "C13") (pin "2") (pinfunction "2_2") (pintype "passive"))
      (node (ref "C14") (pin "1") (pinfunction "1_1") (pintype "passive"))
      (node (ref "C15") (pin "-") (pinfunction "-_-") (pintype "passive"))
      (node (ref "C18") (pin "-") (pinfunction "-_-") (pintype "passive"))
      (node (ref "C19") (pin "+") (pinfunction "+_+") (pintype "passive"))
      (node (ref "C22") (pin "2") (pinfunction "2_2") (pintype "passive"))
      (node (ref "C23") (pin "2") (pinfunction "2_2") (pintype "passive"))
      (node (ref "C24") (pin "1") (pinfunction "1_1") (pintype "passive"))
      (node (ref "C25") (pin "2") (pinfunction "2_2") (pintype "passive"))
      (node (ref "C26") (pin "2") (pinfunction "2_2") (pintype "passive"))
      (node (ref "C29") (pin "-") (pinfunction "-_-") (pintype "passive"))
      (node (ref "C3") (pin "1") (pinfunction "1_1") (pintype "passive"))
      (node (ref "C30") (pin "+") (pinfunction "+_+") (pintype "passive"))
      (node (ref "C33") (pin "-") (pinfunction "-_-") (pintype "passive"))
      (node (ref "C34") (pin "2") (pinfunction "2_2") (pintype "passive"))
      (node (ref "C35") (pin "2") (pinfunction "2_2") (pintype "passive"))
      (node (ref "C36") (pin "2") (pinfunction "2_2") (pintype "passive"))
      (node (ref "C37") (pin "2") (pinfunction "2_2") (pintype "passive"))
      (node (ref "C38") (pin "2") (pinfunction "2_2") (pintype "passive"))
      (node (ref "C39") (pin "1") (pinfunction "1_1") (pintype "passive"))
      (node (ref "C40") (pin "1") (pinfunction "1_1") (pintype "passive"))
      (node (ref "C41") (pin "1") (pinfunction "1_1") (pintype "passive"))
      (node (ref "C42") (pin "+") (pinfunction "+_+") (pintype "passive"))
      (node (ref "C43") (pin "1") (pinfunction "1_1") (pintype "passive"))
      (node (ref "C44") (pin "1") (pinfunction "1_1") (pintype "passive"))
      (node (ref "C45") (pin "1") (pinfunction "1_1") (pintype "passive"))
      (node (ref "C46") (pin "-") (pinfunction "-_-") (pintype "passive"))
      (node (ref "C47") (pin "-") (pinfunction "-_-") (pintype "passive"))
      (node (ref "C48") (pin "-") (pinfunction "-_-") (pintype "passive"))
      (node (ref "C49") (pin "-") (pinfunction "-_-") (pintype "passive"))
      (node (ref "C5") (pin "2") (pinfunction "2_2") (pintype "passive"))
      (node (ref "C50") (pin "-") (pinfunction "-_-") (pintype "passive"))
      (node (ref "C51") (pin "-") (pinfunction "-_-") (pintype "passive"))
      (node (ref "C52") (pin "-") (pinfunction "-_-") (pintype "passive"))
      (node (ref "C53") (pin "-") (pinfunction "-_-") (pintype "passive"))
      (node (ref "C54") (pin "+") (pinfunction "+_+") (pintype "passive"))
      (node (ref "C55") (pin "2") (pinfunction "2_2") (pintype "passive"))
      (node (ref "C56") (pin "-") (pinfunction "-_-") (pintype "passive"))
      (node (ref "C57") (pin "1") (pinfunction "1_1") (pintype "passive"))
      (node (ref "C58") (pin "-") (pinfunction "-_-") (pintype "passive"))
      (node (ref "C59") (pin "-") (pinfunction "-_-") (pintype "passive"))
      (node (ref "C6") (pin "2") (pinfunction "2_2") (pintype "passive"))
      (node (ref "C60") (pin "-") (pinfunction "-_-") (pintype "passive"))
      (node (ref "C61") (pin "-") (pinfunction "-_-") (pintype "passive"))
      (node (ref "C62") (pin "-") (pinfunction "-_-") (pintype "passive"))
      (node (ref "C63") (pin "-") (pinfunction "-_-") (pintype "passive"))
      (node (ref "C64") (pin "-") (pinfunction "-_-") (pintype "passive"))
      (node (ref "C65") (pin "+") (pinfunction "+_+") (pintype "passive"))
      (node (ref "C66") (pin "1") (pinfunction "1_1") (pintype "passive"))
      (node (ref "C67") (pin "1") (pinfunction "1_1") (pintype "passive"))
      (node (ref "C68") (pin "-") (pinfunction "-_-") (pintype "passive"))
      (node (ref "C69") (pin "+") (pinfunction "+_+") (pintype "passive"))
      (node (ref "C7") (pin "-") (pinfunction "-_-") (pintype "passive"))
      (node (ref "C70") (pin "1") (pinfunction "1_1") (pintype "passive"))
      (node (ref "C71") (pin "1") (pinfunction "1_1") (pintype "passive"))
      (node (ref "C72") (pin "-") (pinfunction "-_-") (pintype "passive"))
      (node (ref "C73") (pin "+") (pinfunction "+_+") (pintype "passive"))
      (node (ref "C74") (pin "1") (pinfunction "1_1") (pintype "passive"))
      (node (ref "C75") (pin "1") (pinfunction "1_1") (pintype "passive"))
      (node (ref "C8") (pin "+") (pinfunction "+_+") (pintype "passive"))
      (node (ref "D3") (pin "A") (pinfunction "A_A") (pintype "passive"))
      (node (ref "D5") (pin "A") (pinfunction "A_A") (pintype "passive"))
      (node (ref "D6") (pin "C") (pinfunction "C_C") (pintype "passive"))
      (node (ref "IC1") (pin "3") (pinfunction "GND_3") (pintype "power_in"))
      (node (ref "IC10") (pin "4") (pinfunction "V-_4") (pintype "power_in"))
      (node (ref "IC11") (pin "4") (pinfunction "V-_4") (pintype "power_in"))
      (node (ref "IC12") (pin "4") (pinfunction "V-_4") (pintype "power_in"))
      (node (ref "IC14") (pin "4") (pinfunction "V-_4") (pintype "power_in"))
      (node (ref "IC15") (pin "4") (pinfunction "V-_4") (pintype "power_in"))
      (node (ref "IC16") (pin "4") (pinfunction "V-_4") (pintype "power_in"))
      (node (ref "IC17") (pin "4") (pinfunction "V-_4") (pintype "power_in"))
      (node (ref "IC2") (pin "4") (pinfunction "V-_4") (pintype "power_in"))
      (node (ref "IC3") (pin "4") (pinfunction "V-_4") (pintype "power_in"))
      (node (ref "IC4") (pin "4") (pinfunction "V-_4") (pintype "power_in"))
      (node (ref "IC5") (pin "4") (pinfunction "V-_4") (pintype "power_in"))
      (node (ref "IC6") (pin "4") (pinfunction "V-_4") (pintype "power_in"))
      (node (ref "IC8") (pin "2") (pinfunction "GND_2") (pintype "passive"))
      (node (ref "J1") (pin "2") (pinfunction "2_2") (pintype "passive"))
      (node (ref "R15") (pin "1") (pinfunction "1_1") (pintype "passive"))
      (node (ref "R21") (pin "1") (pinfunction "1_1") (pintype "passive"))
      (node (ref "R22") (pin "1") (pinfunction "1_1") (pintype "passive"))
      (node (ref "R24") (pin "1") (pinfunction "1_1") (pintype "passive"))
      (node (ref "R36") (pin "1") (pinfunction "1_1") (pintype "passive"))
      (node (ref "R37") (pin "1") (pinfunction "1_1") (pintype "passive"))
      (node (ref "R39") (pin "1") (pinfunction "1_1") (pintype "passive"))
      (node (ref "R48") (pin "1") (pinfunction "1_1") (pintype "passive"))
      (node (ref "R5") (pin "2") (pinfunction "2_2") (pintype "passive"))
      (node (ref "R7") (pin "1") (pinfunction "1_1") (pintype "passive"))
    )
    (net (code "13") (name "Net-(+5V-PadA)") (class "Default")
      (node (ref "+5V") (pin "A") (pinfunction "A_A") (pintype "passive"))
      (node (ref "R14") (pin "1") (pinfunction "1_1") (pintype "passive"))
    )
    (net (code "14") (name "Net-(+9V-PadA)") (class "Default")
      (node (ref "+9V") (pin "A") (pinfunction "A_A") (pintype "passive"))
      (node (ref "R4") (pin "1") (pinfunction "1_1") (pintype "passive"))
    )
    (net (code "15") (name "Net-(-9V-PadA)") (class "Default")
      (node (ref "-9V") (pin "A") (pinfunction "A_A") (pintype "passive"))
      (node (ref "R5") (pin "1") (pinfunction "1_1") (pintype "passive"))
    )
    (net (code "16") (name "Net-(C1-Pad1)") (class "Default")
      (node (ref "C1") (pin "1") (pinfunction "1_1") (pintype "passive"))
      (node (ref "R8") (pin "1") (pinfunction "1_1") (pintype "passive"))
      (node (ref "R9") (pin "2") (pinfunction "2_2") (pintype "passive"))
    )
    (net (code "17") (name "Net-(C9-Pad1)") (class "Default")
      (node (ref "C9") (pin "1") (pinfunction "1_1") (pintype "passive"))
      (node (ref "R10") (pin "1") (pinfunction "1_1") (pintype "passive"))
      (node (ref "R11") (pin "2") (pinfunction "2_2") (pintype "passive"))
    )
    (net (code "18") (name "Net-(C16-Pad1)") (class "Default")
      (node (ref "C16") (pin "1") (pinfunction "1_1") (pintype "passive"))
      (node (ref "R25") (pin "1") (pinfunction "1_1") (pintype "passive"))
      (node (ref "R26") (pin "2") (pinfunction "2_2") (pintype "passive"))
    )
    (net (code "19") (name "Net-(C20-Pad1)") (class "Default")
      (node (ref "C20") (pin "1") (pinfunction "1_1") (pintype "passive"))
      (node (ref "R27") (pin "1") (pinfunction "1_1") (pintype "passive"))
      (node (ref "R28") (pin "2") (pinfunction "2_2") (pintype "passive"))
    )
    (net (code "20") (name "Net-(C27-Pad1)") (class "Default")
      (node (ref "C27") (pin "1") (pinfunction "1_1") (pintype "passive"))
      (node (ref "R40") (pin "1") (pinfunction "1_1") (pintype "passive"))
      (node (ref "R41") (pin "2") (pinfunction "2_2") (pintype "passive"))
    )
    (net (code "21") (name "Net-(C31-Pad1)") (class "Default")
      (node (ref "C31") (pin "1") (pinfunction "1_1") (pintype "passive"))
      (node (ref "R42") (pin "1") (pinfunction "1_1") (pintype "passive"))
      (node (ref "R43") (pin "2") (pinfunction "2_2") (pintype "passive"))
    )
    (net (code "22") (name "Net-(IC1-CAP+)") (class "Default")
      (node (ref "C2") (pin "+") (pinfunction "+_+") (pintype "passive"))
      (node (ref "IC1") (pin "2") (pinfunction "CAP+_2") (pintype "passive"))
    )
    (net (code "23") (name "Net-(IC1-CAP-)") (class "Default")
      (node (ref "C2") (pin "-") (pinfunction "-_-") (pintype "passive"))
      (node (ref "IC1") (pin "4") (pinfunction "CAP-_4") (pintype "passive"))
    )
    (net (code "24") (name "Net-(IC1-VIN)") (class "Default")
      (node (ref "7809L") (pin "IN") (pinfunction "IN_IN") (pintype "input"))
      (node (ref "C14") (pin "2") (pinfunction "2_2") (pintype "passive"))
      (node (ref "C15") (pin "+") (pinfunction "+_+") (pintype "passive"))
      (node (ref "C53") (pin "+") (pinfunction "+_+") (pintype "passive"))
      (node (ref "C57") (pin "2") (pinfunction "2_2") (pintype "passive"))
      (node (ref "C63") (pin "+") (pinfunction "+_+") (pintype "passive"))
      (node (ref "D1") (pin "C") (pinfunction "C_C") (pintype "passive"))
      (node (ref "D2") (pin "C") (pinfunction "C_C") (pintype "passive"))
      (node (ref "IC1") (pin "8") (pinfunction "VIN_8") (pintype "input"))
      (node (ref "IC8") (pin "3") (pinfunction "VI_3") (pintype "input"))
      (node (ref "J1") (pin "3") (pinfunction "3_3") (pintype "passive"))
    )
    (net (code "25") (name "Net-(IC1-VOUT)") (class "Default")
      (node (ref "7909L") (pin "IN") (pinfunction "IN_IN") (pintype "input"))
      (node (ref "C12") (pin "-") (pinfunction "-_-") (pintype "passive"))
      (node (ref "C54") (pin "-") (pinfunction "-_-") (pintype "passive"))
      (node (ref "C55") (pin "1") (pinfunction "1_1") (pintype "passive"))
      (node (ref "D4") (pin "A") (pinfunction "A_A") (pintype "passive"))
      (node (ref "IC1") (pin "5") (pinfunction "VOUT_5") (pintype "output"))
    )
    (net (code "26") (name "Net-(IC2-+IN)") (class "Default")
      (node (ref "C4") (pin "1") (pinfunction "1_1") (pintype "passive"))
      (node (ref "IC2") (pin "3") (pinfunction "+IN_3") (pintype "input"))
      (node (ref "R9") (pin "1") (pinfunction "1_1") (pintype "passive"))
    )
    (net (code "27") (name "Net-(IC2--IN)") (class "Default")
      (node (ref "C1") (pin "2") (pinfunction "2_2") (pintype "passive"))
      (node (ref "IC2") (pin "2") (pinfunction "-IN_2") (pintype "input"))
      (node (ref "IC2") (pin "6") (pinfunction "OUT_6") (pintype "output"))
      (node (ref "R10") (pin "2") (pinfunction "2_2") (pintype "passive"))
    )
    (net (code "28") (name "Net-(IC3-+IN)") (class "Default")
      (node (ref "IC3") (pin "3") (pinfunction "+IN_3") (pintype "input"))
      (node (ref "R6") (pin "1") (pinfunction "1_1") (pintype "passive"))
      (node (ref "R7") (pin "2") (pinfunction "2_2") (pintype "passive"))
    )
    (net (code "29") (name "Net-(IC3--IN)") (class "Default")
      (node (ref "C10") (pin "2") (pinfunction "2_2") (pintype "passive"))
      (node (ref "C4") (pin "2") (pinfunction "2_2") (pintype "passive"))
      (node (ref "IC3") (pin "2") (pinfunction "-IN_2") (pintype "input"))
      (node (ref "IC3") (pin "6") (pinfunction "OUT_6") (pintype "output"))
      (node (ref "IC7") (pin "7") (pinfunction "REF_7") (pintype "passive"))
      (node (ref "R12") (pin "2") (pinfunction "2_2") (pintype "passive"))
    )
    (net (code "30") (name "Net-(IC4-+IN)") (class "Default")
      (node (ref "C10") (pin "1") (pinfunction "1_1") (pintype "passive"))
      (node (ref "IC4") (pin "3") (pinfunction "+IN_3") (pintype "input"))
      (node (ref "R11") (pin "1") (pinfunction "1_1") (pintype "passive"))
    )
    (net (code "31") (name "Net-(IC4--IN)") (class "Default")
      (node (ref "C9") (pin "2") (pinfunction "2_2") (pintype "passive"))
      (node (ref "IC4") (pin "2") (pinfunction "-IN_2") (pintype "input"))
      (node (ref "IC4") (pin "6") (pinfunction "OUT_6") (pintype "output"))
      (node (ref "IC5") (pin "3") (pinfunction "+IN_3") (pintype "input"))
    )
    (net (code "32") (name "Net-(IC5--IN)") (class "Default")
      (node (ref "IC5") (pin "2") (pinfunction "-IN_2") (pintype "input"))
      (node (ref "R12") (pin "1") (pinfunction "1_1") (pintype "passive"))
      (node (ref "R13") (pin "2") (pinfunction "2_2") (pintype "passive"))
      (node (ref "R16") (pin "2") (pinfunction "2_2") (pintype "passive"))
      (node (ref "R17") (pin "2") (pinfunction "2_2") (pintype "passive"))
    )
    (net (code "33") (name "Net-(IC6-+IN)") (class "Default")
      (node (ref "C17") (pin "1") (pinfunction "1_1") (pintype "passive"))
      (node (ref "IC6") (pin "3") (pinfunction "+IN_3") (pintype "input"))
      (node (ref "R26") (pin "1") (pinfunction "1_1") (pintype "passive"))
    )
    (net (code "34") (name "Net-(IC6--IN)") (class "Default")
      (node (ref "C16") (pin "2") (pinfunction "2_2") (pintype "passive"))
      (node (ref "IC6") (pin "2") (pinfunction "-IN_2") (pintype "input"))
      (node (ref "IC6") (pin "6") (pinfunction "OUT_6") (pintype "output"))
      (node (ref "R27") (pin "2") (pinfunction "2_2") (pintype "passive"))
    )
    (net (code "35") (name "Net-(IC7-+GS)") (class "Default")
      (node (ref "IC7") (pin "2") (pinfunction "+GS_2") (pintype "input"))
      (node (ref "IC7") (pin "6") (pinfunction "+RG_6") (pintype "passive"))
      (node (ref "R1") (pin "1") (pinfunction "1_1") (pintype "passive"))
    )
    (net (code "36") (name "Net-(IC7-+IN)") (class "Default")
      (node (ref "IC7") (pin "1") (pinfunction "+IN_1") (pintype "input"))
      (node (ref "L2") (pin "2") (pinfunction "2_2") (pintype "passive"))
      (node (ref "R3") (pin "1") (pinfunction "1_1") (pintype "passive"))
    )
    (net (code "37") (name "Net-(IC7--GS)") (class "Default")
      (node (ref "IC7") (pin "13") (pinfunction "-RG_13") (pintype "passive"))
      (node (ref "IC7") (pin "15") (pinfunction "-GS_15") (pintype "input"))
      (node (ref "R1") (pin "2") (pinfunction "2_2") (pintype "passive"))
    )
    (net (code "38") (name "Net-(IC7--IN)") (class "Default")
      (node (ref "IC7") (pin "16") (pinfunction "-IN_16") (pintype "input"))
      (node (ref "L1") (pin "2") (pinfunction "2_2") (pintype "passive"))
      (node (ref "R2") (pin "1") (pinfunction "1_1") (pintype "passive"))
    )
    (net (code "39") (name "Net-(IC7-OUT)") (class "Default")
      (node (ref "IC7") (pin "10") (pinfunction "OUT_10") (pintype "output"))
      (node (ref "IC7") (pin "11") (pinfunction "SENSE_11") (pintype "input"))
      (node (ref "R8") (pin "2") (pinfunction "2_2") (pintype "passive"))
    )
    (net (code "40") (name "Net-(IC9--IN)") (class "Default")
      (node (ref "IC9") (pin "2") (pinfunction "-IN_2") (pintype "input"))
      (node (ref "IC9") (pin "6") (pinfunction "OUT_6") (pintype "output"))
      (node (ref "L2") (pin "1") (pinfunction "1_1") (pintype "passive"))
      (node (ref "R21") (pin "2") (pinfunction "2_2") (pintype "passive"))
      (node (ref "R3") (pin "2") (pinfunction "2_2") (pintype "passive"))
    )
    (net (code "41") (name "Net-(IC10-+IN)") (class "Default")
      (node (ref "IC10") (pin "3") (pinfunction "+IN_3") (pintype "input"))
      (node (ref "R23") (pin "1") (pinfunction "1_1") (pintype "passive"))
      (node (ref "R24") (pin "2") (pinfunction "2_2") (pintype "passive"))
    )
    (net (code "42") (name "Net-(IC10--IN)") (class "Default")
      (node (ref "C17") (pin "2") (pinfunction "2_2") (pintype "passive"))
      (node (ref "C21") (pin "2") (pinfunction "2_2") (pintype "passive"))
      (node (ref "IC10") (pin "2") (pinfunction "-IN_2") (pintype "input"))
      (node (ref "IC10") (pin "6") (pinfunction "OUT_6") (pintype "output"))
      (node (ref "IC13") (pin "7") (pinfunction "REF_7") (pintype "passive"))
      (node (ref "R29") (pin "2") (pinfunction "2_2") (pintype "passive"))
    )
    (net (code "43") (name "Net-(IC11-+IN)") (class "Default")
      (node (ref "C21") (pin "1") (pinfunction "1_1") (pintype "passive"))
      (node (ref "IC11") (pin "3") (pinfunction "+IN_3") (pintype "input"))
      (node (ref "R28") (pin "1") (pinfunction "1_1") (pintype "passive"))
    )
    (net (code "44") (name "Net-(IC11--IN)") (class "Default")
      (node (ref "C20") (pin "2") (pinfunction "2_2") (pintype "passive"))
      (node (ref "IC11") (pin "2") (pinfunction "-IN_2") (pintype "input"))
      (node (ref "IC11") (pin "6") (pinfunction "OUT_6") (pintype "output"))
      (node (ref "IC12") (pin "3") (pinfunction "+IN_3") (pintype "input"))
    )
    (net (code "45") (name "Net-(IC12--IN)") (class "Default")
      (node (ref "IC12") (pin "2") (pinfunction "-IN_2") (pintype "input"))
      (node (ref "R29") (pin "1") (pinfunction "1_1") (pintype "passive"))
      (node (ref "R30") (pin "2") (pinfunction "2_2") (pintype "passive"))
      (node (ref "R31") (pin "2") (pinfunction "2_2") (pintype "passive"))
      (node (ref "R32") (pin "2") (pinfunction "2_2") (pintype "passive"))
    )
    (net (code "46") (name "Net-(IC13-+GS)") (class "Default")
      (node (ref "IC13") (pin "2") (pinfunction "+GS_2") (pintype "input"))
      (node (ref "IC13") (pin "6") (pinfunction "+RG_6") (pintype "passive"))
      (node (ref "R18") (pin "1") (pinfunction "1_1") (pintype "passive"))
    )
    (net (code "47") (name "Net-(IC13-+IN)") (class "Default")
      (node (ref "IC13") (pin "1") (pinfunction "+IN_1") (pintype "input"))
      (node (ref "L4") (pin "2") (pinfunction "2_2") (pintype "passive"))
      (node (ref "R20") (pin "1") (pinfunction "1_1") (pintype "passive"))
    )
    (net (code "48") (name "Net-(IC13--GS)") (class "Default")
      (node (ref "IC13") (pin "13") (pinfunction "-RG_13") (pintype "passive"))
      (node (ref "IC13") (pin "15") (pinfunction "-GS_15") (pintype "input"))
      (node (ref "R18") (pin "2") (pinfunction "2_2") (pintype "passive"))
    )
    (net (code "49") (name "Net-(IC13--IN)") (class "Default")
      (node (ref "IC13") (pin "16") (pinfunction "-IN_16") (pintype "input"))
      (node (ref "L3") (pin "2") (pinfunction "2_2") (pintype "passive"))
      (node (ref "R19") (pin "1") (pinfunction "1_1") (pintype "passive"))
    )
    (net (code "50") (name "Net-(IC13-OUT)") (class "Default")
      (node (ref "IC13") (pin "10") (pinfunction "OUT_10") (pintype "output"))
      (node (ref "IC13") (pin "11") (pinfunction "SENSE_11") (pintype "input"))
      (node (ref "R25") (pin "2") (pinfunction "2_2") (pintype "passive"))
    )
    (net (code "51") (name "Net-(IC14-+IN)") (class "Default")
      (node (ref "C28") (pin "1") (pinfunction "1_1") (pintype "passive"))
      (node (ref "IC14") (pin "3") (pinfunction "+IN_3") (pintype "input"))
      (node (ref "R41") (pin "1") (pinfunction "1_1") (pintype "passive"))
    )
    (net (code "52") (name "Net-(IC14--IN)") (class "Default")
      (node (ref "C27") (pin "2") (pinfunction "2_2") (pintype "passive"))
      (node (ref "IC14") (pin "2") (pinfunction "-IN_2") (pintype "input"))
      (node (ref "IC14") (pin "6") (pinfunction "OUT_6") (pintype "output"))
      (node (ref "R42") (pin "2") (pinfunction "2_2") (pintype "passive"))
    )
    (net (code "53") (name "Net-(IC15-+IN)") (class "Default")
      (node (ref "IC15") (pin "3") (pinfunction "+IN_3") (pintype "input"))
      (node (ref "R38") (pin "1") (pinfunction "1_1") (pintype "passive"))
      (node (ref "R39") (pin "2") (pinfunction "2_2") (pintype "passive"))
    )
    (net (code "54") (name "Net-(IC15--IN)") (class "Default")
      (node (ref "C28") (pin "2") (pinfunction "2_2") (pintype "passive"))
      (node (ref "C32") (pin "2") (pinfunction "2_2") (pintype "passive"))
      (node (ref "IC15") (pin "2") (pinfunction "-IN_2") (pintype "input"))
      (node (ref "IC15") (pin "6") (pinfunction "OUT_6") (pintype "output"))
      (node (ref "IC18") (pin "7") (pinfunction "REF_7") (pintype "passive"))
      (node (ref "R44") (pin "2") (pinfunction "2_2") (pintype "passive"))
    )
    (net (code "55") (name "Net-(IC16-+IN)") (class "Default")
      (node (ref "C32") (pin "1") (pinfunction "1_1") (pintype "passive"))
      (node (ref "IC16") (pin "3") (pinfunction "+IN_3") (pintype "input"))
      (node (ref "R43") (pin "1") (pinfunction "1_1") (pintype "passive"))
    )
    (net (code "56") (name "Net-(IC16--IN)") (class "Default")
      (node (ref "C31") (pin "2") (pinfunction "2_2") (pintype "passive"))
      (node (ref "IC16") (pin "2") (pinfunction "-IN_2") (pintype "input"))
      (node (ref "IC16") (pin "6") (pinfunction "OUT_6") (pintype "output"))
      (node (ref "IC17") (pin "3") (pinfunction "+IN_3") (pintype "input"))
    )
    (net (code "57") (name "Net-(IC17--IN)") (class "Default")
      (node (ref "IC17") (pin "2") (pinfunction "-IN_2") (pintype "input"))
      (node (ref "R44") (pin "1") (pinfunction "1_1") (pintype "passive"))
      (node (ref "R45") (pin "2") (pinfunction "2_2") (pintype "passive"))
      (node (ref "R46") (pin "2") (pinfunction "2_2") (pintype "passive"))
      (node (ref "R47") (pin "2") (pinfunction "2_2") (pintype "passive"))
    )
    (net (code "58") (name "Net-(IC18-+GS)") (class "Default")
      (node (ref "IC18") (pin "2") (pinfunction "+GS_2") (pintype "input"))
      (node (ref "IC18") (pin "6") (pinfunction "+RG_6") (pintype "passive"))
      (node (ref "R33") (pin "1") (pinfunction "1_1") (pintype "passive"))
    )
    (net (code "59") (name "Net-(IC18-+IN)") (class "Default")
      (node (ref "IC18") (pin "1") (pinfunction "+IN_1") (pintype "input"))
      (node (ref "L6") (pin "2") (pinfunction "2_2") (pintype "passive"))
      (node (ref "R35") (pin "1") (pinfunction "1_1") (pintype "passive"))
    )
    (net (code "60") (name "Net-(IC18--GS)") (class "Default")
      (node (ref "IC18") (pin "13") (pinfunction "-RG_13") (pintype "passive"))
      (node (ref "IC18") (pin "15") (pinfunction "-GS_15") (pintype "input"))
      (node (ref "R33") (pin "2") (pinfunction "2_2") (pintype "passive"))
    )
    (net (code "61") (name "Net-(IC18--IN)") (class "Default")
      (node (ref "IC18") (pin "16") (pinfunction "-IN_16") (pintype "input"))
      (node (ref "L5") (pin "2") (pinfunction "2_2") (pintype "passive"))
      (node (ref "R34") (pin "1") (pinfunction "1_1") (pintype "passive"))
    )
    (net (code "62") (name "Net-(IC18-OUT)") (class "Default")
      (node (ref "IC18") (pin "10") (pinfunction "OUT_10") (pintype "output"))
      (node (ref "IC18") (pin "11") (pinfunction "SENSE_11") (pintype "input"))
      (node (ref "R40") (pin "2") (pinfunction "2_2") (pintype "passive"))
    )
    (net (code "63") (name "Net-(IC19--IN)") (class "Default")
      (node (ref "IC19") (pin "2") (pinfunction "-IN_2") (pintype "input"))
      (node (ref "IC19") (pin "6") (pinfunction "OUT_6") (pintype "output"))
      (node (ref "L4") (pin "1") (pinfunction "1_1") (pintype "passive"))
      (node (ref "R20") (pin "2") (pinfunction "2_2") (pintype "passive"))
      (node (ref "R36") (pin "2") (pinfunction "2_2") (pintype "passive"))
    )
    (net (code "64") (name "Net-(IC20--IN)") (class "Default")
      (node (ref "IC20") (pin "2") (pinfunction "-IN_2") (pintype "input"))
      (node (ref "IC20") (pin "6") (pinfunction "OUT_6") (pintype "output"))
      (node (ref "L6") (pin "1") (pinfunction "1_1") (pintype "passive"))
      (node (ref "R35") (pin "2") (pinfunction "2_2") (pintype "passive"))
      (node (ref "R37") (pin "2") (pinfunction "2_2") (pintype "passive"))
    )
    (net (code "65") (name "Net-(JP1-Pad1)") (class "Default")
      (node (ref "JP1") (pin "1") (pinfunction "1_1") (pintype "passive"))
      (node (ref "R13") (pin "1") (pinfunction "1_1") (pintype "passive"))
    )
    (net (code "66") (name "Net-(JP2-Pad1)") (class "Default")
      (node (ref "JP2") (pin "1") (pinfunction "1_1") (pintype "passive"))
      (node (ref "R16") (pin "1") (pinfunction "1_1") (pintype "passive"))
    )
    (net (code "67") (name "Net-(JP3-Pad1)") (class "Default")
      (node (ref "JP3") (pin "1") (pinfunction "1_1") (pintype "passive"))
      (node (ref "R17") (pin "1") (pinfunction "1_1") (pintype "passive"))
    )
    (net (code "68") (name "Net-(JP4-Pad1)") (class "Default")
      (node (ref "JP4") (pin "1") (pinfunction "1_1") (pintype "passive"))
      (node (ref "R30") (pin "1") (pinfunction "1_1") (pintype "passive"))
    )
    (net (code "69") (name "Net-(JP5-Pad1)") (class "Default")
      (node (ref "JP5") (pin "1") (pinfunction "1_1") (pintype "passive"))
      (node (ref "R31") (pin "1") (pinfunction "1_1") (pintype "passive"))
    )
    (net (code "70") (name "Net-(JP6-Pad1)") (class "Default")
      (node (ref "JP6") (pin "1") (pinfunction "1_1") (pintype "passive"))
      (node (ref "R32") (pin "1") (pinfunction "1_1") (pintype "passive"))
    )
    (net (code "71") (name "Net-(JP7-Pad1)") (class "Default")
      (node (ref "JP7") (pin "1") (pinfunction "1_1") (pintype "passive"))
      (node (ref "R45") (pin "1") (pinfunction "1_1") (pintype "passive"))
    )
    (net (code "72") (name "Net-(JP8-Pad1)") (class "Default")
      (node (ref "JP8") (pin "1") (pinfunction "1_1") (pintype "passive"))
      (node (ref "R46") (pin "1") (pinfunction "1_1") (pintype "passive"))
    )
    (net (code "73") (name "Net-(JP9-Pad1)") (class "Default")
      (node (ref "JP9") (pin "1") (pinfunction "1_1") (pintype "passive"))
      (node (ref "R47") (pin "1") (pinfunction "1_1") (pintype "passive"))
    )
    (net (code "74") (name "VCC") (class "Default")
      (node (ref "C11") (pin "1") (pinfunction "1_1") (pintype "passive"))
      (node (ref "C13") (pin "1") (pinfunction "1_1") (pintype "passive"))
      (node (ref "C22") (pin "1") (pinfunction "1_1") (pintype "passive"))
      (node (ref "C23") (pin "1") (pinfunction "1_1") (pintype "passive"))
      (node (ref "C24") (pin "2") (pinfunction "2_2") (pintype "passive"))
      (node (ref "C25") (pin "1") (pinfunction "1_1") (pintype "passive"))
      (node (ref "C26") (pin "1") (pinfunction "1_1") (pintype "passive"))
      (node (ref "C34") (pin "1") (pinfunction "1_1") (pintype "passive"))
      (node (ref "C35") (pin "1") (pinfunction "1_1") (pintype "passive"))
      (node (ref "C36") (pin "1") (pinfunction "1_1") (pintype "passive"))
      (node (ref "C37") (pin "1") (pinfunction "1_1") (pintype "passive"))
      (node (ref "C46") (pin "+") (pinfunction "+_+") (pintype "passive"))
      (node (ref "C47") (pin "+") (pinfunction "+_+") (pintype "passive"))
      (node (ref "C48") (pin "+") (pinfunction "+_+") (pintype "passive"))
      (node (ref "C49") (pin "+") (pinfunction "+_+") (pintype "passive"))
      (node (ref "C5") (pin "1") (pinfunction "1_1") (pintype "passive"))
      (node (ref "C50") (pin "+") (pinfunction "+_+") (pintype "passive"))
      (node (ref "C51") (pin "+") (pinfunction "+_+") (pintype "passive"))
      (node (ref "C52") (pin "+") (pinfunction "+_+") (pintype "passive"))
      (node (ref "C56") (pin "+") (pinfunction "+_+") (pintype "passive"))
      (node (ref "C58") (pin "+") (pinfunction "+_+") (pintype "passive"))
      (node (ref "C59") (pin "+") (pinfunction "+_+") (pintype "passive"))
      (node (ref "C6") (pin "1") (pinfunction "1_1") (pintype "passive"))
      (node (ref "C60") (pin "+") (pinfunction "+_+") (pintype "passive"))
      (node (ref "C61") (pin "+") (pinfunction "+_+") (pintype "passive"))
      (node (ref "C62") (pin "+") (pinfunction "+_+") (pintype "passive"))
      (node (ref "D2") (pin "A") (pinfunction "A_A") (pintype "passive"))
      (node (ref "D3") (pin "C") (pinfunction "C_C") (pintype "passive"))
      (node (ref "IC10") (pin "7") (pinfunction "V+_7") (pintype "power_in"))
      (node (ref "IC11") (pin "7") (pinfunction "V+_7") (pintype "power_in"))
      (node (ref "IC12") (pin "7") (pinfunction "V+_7") (pintype "power_in"))
      (node (ref "IC14") (pin "7") (pinfunction "V+_7") (pintype "power_in"))
      (node (ref "IC15") (pin "7") (pinfunction "V+_7") (pintype "power_in"))
      (node (ref "IC16") (pin "7") (pinfunction "V+_7") (pintype "power_in"))
      (node (ref "IC17") (pin "7") (pinfunction "V+_7") (pintype "power_in"))
      (node (ref "IC2") (pin "7") (pinfunction "V+_7") (pintype "power_in"))
      (node (ref "IC3") (pin "7") (pinfunction "V+_7") (pintype "power_in"))
      (node (ref "IC4") (pin "7") (pinfunction "V+_7") (pintype "power_in"))
      (node (ref "IC5") (pin "7") (pinfunction "V+_7") (pintype "power_in"))
      (node (ref "IC6") (pin "7") (pinfunction "V+_7") (pintype "power_in"))
      (node (ref "IC8") (pin "1") (pinfunction "VO_1") (pintype "passive"))
      (node (ref "R14") (pin "2") (pinfunction "2_2") (pintype "passive"))
      (node (ref "R23") (pin "2") (pinfunction "2_2") (pintype "passive"))
      (node (ref "R38") (pin "2") (pinfunction "2_2") (pintype "passive"))
      (node (ref "R6") (pin "2") (pinfunction "2_2") (pintype "passive"))
    )
    (net (code "75") (name "unconnected-(ASPOUT-Pad4)") (class "Default")
      (node (ref "ASPOUT") (pin "4") (pinfunction "4_4") (pintype "passive"))
    )
    (net (code "76") (name "unconnected-(GEOIN-Pad7)") (class "Default")
      (node (ref "GEOIN") (pin "7") (pinfunction "7_7") (pintype "passive"))
    )
    (net (code "77") (name "unconnected-(GEOIN-Pad8)") (class "Default")
      (node (ref "GEOIN") (pin "8") (pinfunction "8_8") (pintype "passive"))
    )
    (net (code "78") (name "unconnected-(GEOIN-Pad9)") (class "Default")
      (node (ref "GEOIN") (pin "9") (pinfunction "9_9") (pintype "passive"))
    )
    (net (code "79") (name "unconnected-(GEOIN-Pad10)") (class "Default")
      (node (ref "GEOIN") (pin "10") (pinfunction "10_10") (pintype "passive"))
    )
    (net (code "80") (name "unconnected-(IC1-FB-Pad1)") (class "Default")
      (node (ref "IC1") (pin "1") (pinfunction "FB_1") (pintype "input"))
    )
    (net (code "81") (name "unconnected-(IC1-OSC-Pad7)") (class "Default")
      (node (ref "IC1") (pin "7") (pinfunction "OSC_7") (pintype "output"))
    )
    (net (code "82") (name "unconnected-(IC1-REF-Pad6)") (class "Default")
      (node (ref "IC1") (pin "6") (pinfunction "REF_6") (pintype "input"))
    )
    (net (code "83") (name "unconnected-(IC2-OFF1-Pad1)") (class "Default")
      (node (ref "IC2") (pin "1") (pinfunction "OFF1_1") (pintype "passive"))
    )
    (net (code "84") (name "unconnected-(IC2-OFF2-Pad8)") (class "Default")
      (node (ref "IC2") (pin "8") (pinfunction "OFF2_8") (pintype "passive"))
    )
    (net (code "85") (name "unconnected-(IC3-OFF1-Pad1)") (class "Default")
      (node (ref "IC3") (pin "1") (pinfunction "OFF1_1") (pintype "passive"))
    )
    (net (code "86") (name "unconnected-(IC3-OFF2-Pad8)") (class "Default")
      (node (ref "IC3") (pin "8") (pinfunction "OFF2_8") (pintype "passive"))
    )
    (net (code "87") (name "unconnected-(IC4-OFF1-Pad1)") (class "Default")
      (node (ref "IC4") (pin "1") (pinfunction "OFF1_1") (pintype "passive"))
    )
    (net (code "88") (name "unconnected-(IC4-OFF2-Pad8)") (class "Default")
      (node (ref "IC4") (pin "8") (pinfunction "OFF2_8") (pintype "passive"))
    )
    (net (code "89") (name "unconnected-(IC5-OFF1-Pad1)") (class "Default")
      (node (ref "IC5") (pin "1") (pinfunction "OFF1_1") (pintype "passive"))
    )
    (net (code "90") (name "unconnected-(IC5-OFF2-Pad8)") (class "Default")
      (node (ref "IC5") (pin "8") (pinfunction "OFF2_8") (pintype "passive"))
    )
    (net (code "91") (name "unconnected-(IC6-OFF1-Pad1)") (class "Default")
      (node (ref "IC6") (pin "1") (pinfunction "OFF1_1") (pintype "passive"))
    )
    (net (code "92") (name "unconnected-(IC6-OFF2-Pad8)") (class "Default")
      (node (ref "IC6") (pin "8") (pinfunction "OFF2_8") (pintype "passive"))
    )
    (net (code "93") (name "unconnected-(IC7-+GD-Pad5)") (class "Default")
      (node (ref "IC7") (pin "5") (pinfunction "+GD_5") (pintype "passive"))
    )
    (net (code "94") (name "unconnected-(IC7-+OFFS-Pad3)") (class "Default")
      (node (ref "IC7") (pin "3") (pinfunction "+OFFS_3") (pintype "passive"))
    )
    (net (code "95") (name "unconnected-(IC7--GD-Pad12)") (class "Default")
      (node (ref "IC7") (pin "12") (pinfunction "-GD_12") (pintype "passive"))
    )
    (net (code "96") (name "unconnected-(IC7--OFFS-Pad4)") (class "Default")
      (node (ref "IC7") (pin "4") (pinfunction "-OFFS_4") (pintype "passive"))
    )
    (net (code "97") (name "unconnected-(IC7-G=100-Pad14)") (class "Default")
      (node (ref "IC7") (pin "14") (pinfunction "G=100_14") (pintype "passive"))
    )
    (net (code "98") (name "unconnected-(IC9-OFF1-Pad1)") (class "Default")
      (node (ref "IC9") (pin "1") (pinfunction "OFF1_1") (pintype "passive"))
    )
    (net (code "99") (name "unconnected-(IC9-OFF2-Pad8)") (class "Default")
      (node (ref "IC9") (pin "8") (pinfunction "OFF2_8") (pintype "passive"))
    )
    (net (code "100") (name "unconnected-(IC10-OFF1-Pad1)") (class "Default")
      (node (ref "IC10") (pin "1") (pinfunction "OFF1_1") (pintype "passive"))
    )
    (net (code "101") (name "unconnected-(IC10-OFF2-Pad8)") (class "Default")
      (node (ref "IC10") (pin "8") (pinfunction "OFF2_8") (pintype "passive"))
    )
    (net (code "102") (name "unconnected-(IC11-OFF1-Pad1)") (class "Default")
      (node (ref "IC11") (pin "1") (pinfunction "OFF1_1") (pintype "passive"))
    )
    (net (code "103") (name "unconnected-(IC11-OFF2-Pad8)") (class "Default")
      (node (ref "IC11") (pin "8") (pinfunction "OFF2_8") (pintype "passive"))
    )
    (net (code "104") (name "unconnected-(IC12-OFF1-Pad1)") (class "Default")
      (node (ref "IC12") (pin "1") (pinfunction "OFF1_1") (pintype "passive"))
    )
    (net (code "105") (name "unconnected-(IC12-OFF2-Pad8)") (class "Default")
      (node (ref "IC12") (pin "8") (pinfunction "OFF2_8") (pintype "passive"))
    )
    (net (code "106") (name "unconnected-(IC13-+GD-Pad5)") (class "Default")
      (node (ref "IC13") (pin "5") (pinfunction "+GD_5") (pintype "passive"))
    )
    (net (code "107") (name "unconnected-(IC13-+OFFS-Pad3)") (class "Default")
      (node (ref "IC13") (pin "3") (pinfunction "+OFFS_3") (pintype "passive"))
    )
    (net (code "108") (name "unconnected-(IC13--GD-Pad12)") (class "Default")
      (node (ref "IC13") (pin "12") (pinfunction "-GD_12") (pintype "passive"))
    )
    (net (code "109") (name "unconnected-(IC13--OFFS-Pad4)") (class "Default")
      (node (ref "IC13") (pin "4") (pinfunction "-OFFS_4") (pintype "passive"))
    )
    (net (code "110") (name "unconnected-(IC13-G=100-Pad14)") (class "Default")
      (node (ref "IC13") (pin "14") (pinfunction "G=100_14") (pintype "passive"))
    )
    (net (code "111") (name "unconnected-(IC14-OFF1-Pad1)") (class "Default")
      (node (ref "IC14") (pin "1") (pinfunction "OFF1_1") (pintype "passive"))
    )
    (net (code "112") (name "unconnected-(IC14-OFF2-Pad8)") (class "Default")
      (node (ref "IC14") (pin "8") (pinfunction "OFF2_8") (pintype "passive"))
    )
    (net (code "113") (name "unconnected-(IC15-OFF1-Pad1)") (class "Default")
      (node (ref "IC15") (pin "1") (pinfunction "OFF1_1") (pintype "passive"))
    )
    (net (code "114") (name "unconnected-(IC15-OFF2-Pad8)") (class "Default")
      (node (ref "IC15") (pin "8") (pinfunction "OFF2_8") (pintype "passive"))
    )
    (net (code "115") (name "unconnected-(IC16-OFF1-Pad1)") (class "Default")
      (node (ref "IC16") (pin "1") (pinfunction "OFF1_1") (pintype "passive"))
    )
    (net (code "116") (name "unconnected-(IC16-OFF2-Pad8)") (class "Default")
      (node (ref "IC16") (pin "8") (pinfunction "OFF2_8") (pintype "passive"))
    )
    (net (code "117") (name "unconnected-(IC17-OFF1-Pad1)") (class "Default")
      (node (ref "IC17") (pin "1") (pinfunction "OFF1_1") (pintype "passive"))
    )
    (net (code "118") (name "unconnected-(IC17-OFF2-Pad8)") (class "Default")
      (node (ref "IC17") (pin "8") (pinfunction "OFF2_8") (pintype "passive"))
    )
    (net (code "119") (name "unconnected-(IC18-+GD-Pad5)") (class "Default")
      (node (ref "IC18") (pin "5") (pinfunction "+GD_5") (pintype "passive"))
    )
    (net (code "120") (name "unconnected-(IC18-+OFFS-Pad3)") (class "Default")
      (node (ref "IC18") (pin "3") (pinfunction "+OFFS_3") (pintype "passive"))
    )
    (net (code "121") (name "unconnected-(IC18--GD-Pad12)") (class "Default")
      (node (ref "IC18") (pin "12") (pinfunction "-GD_12") (pintype "passive"))
    )
    (net (code "122") (name "unconnected-(IC18--OFFS-Pad4)") (class "Default")
      (node (ref "IC18") (pin "4") (pinfunction "-OFFS_4") (pintype "passive"))
    )
    (net (code "123") (name "unconnected-(IC18-G=100-Pad14)") (class "Default")
      (node (ref "IC18") (pin "14") (pinfunction "G=100_14") (pintype "passive"))
    )
    (net (code "124") (name "unconnected-(IC19-OFF1-Pad1)") (class "Default")
      (node (ref "IC19") (pin "1") (pinfunction "OFF1_1") (pintype "passive"))
    )
    (net (code "125") (name "unconnected-(IC19-OFF2-Pad8)") (class "Default")
      (node (ref "IC19") (pin "8") (pinfunction "OFF2_8") (pintype "passive"))
    )
    (net (code "126") (name "unconnected-(IC20-OFF1-Pad1)") (class "Default")
      (node (ref "IC20") (pin "1") (pinfunction "OFF1_1") (pintype "passive"))
    )
    (net (code "127") (name "unconnected-(IC20-OFF2-Pad8)") (class "Default")
      (node (ref "IC20") (pin "8") (pinfunction "OFF2_8") (pintype "passive"))
    )
    (net (code "128") (name "unconnected-(J1-Pad1)") (class "Default")
      (node (ref "J1") (pin "1") (pinfunction "1_1") (pintype "passive"))
    )
    (net (code "129") (name "unconnected-(J1-Pad4)") (class "Default")
      (node (ref "J1") (pin "4") (pinfunction "4_4") (pintype "passive"))
    )
  )
)
